# APM9328_CPU.net
KiCad netlist of a schematic drawn in Altium Designer
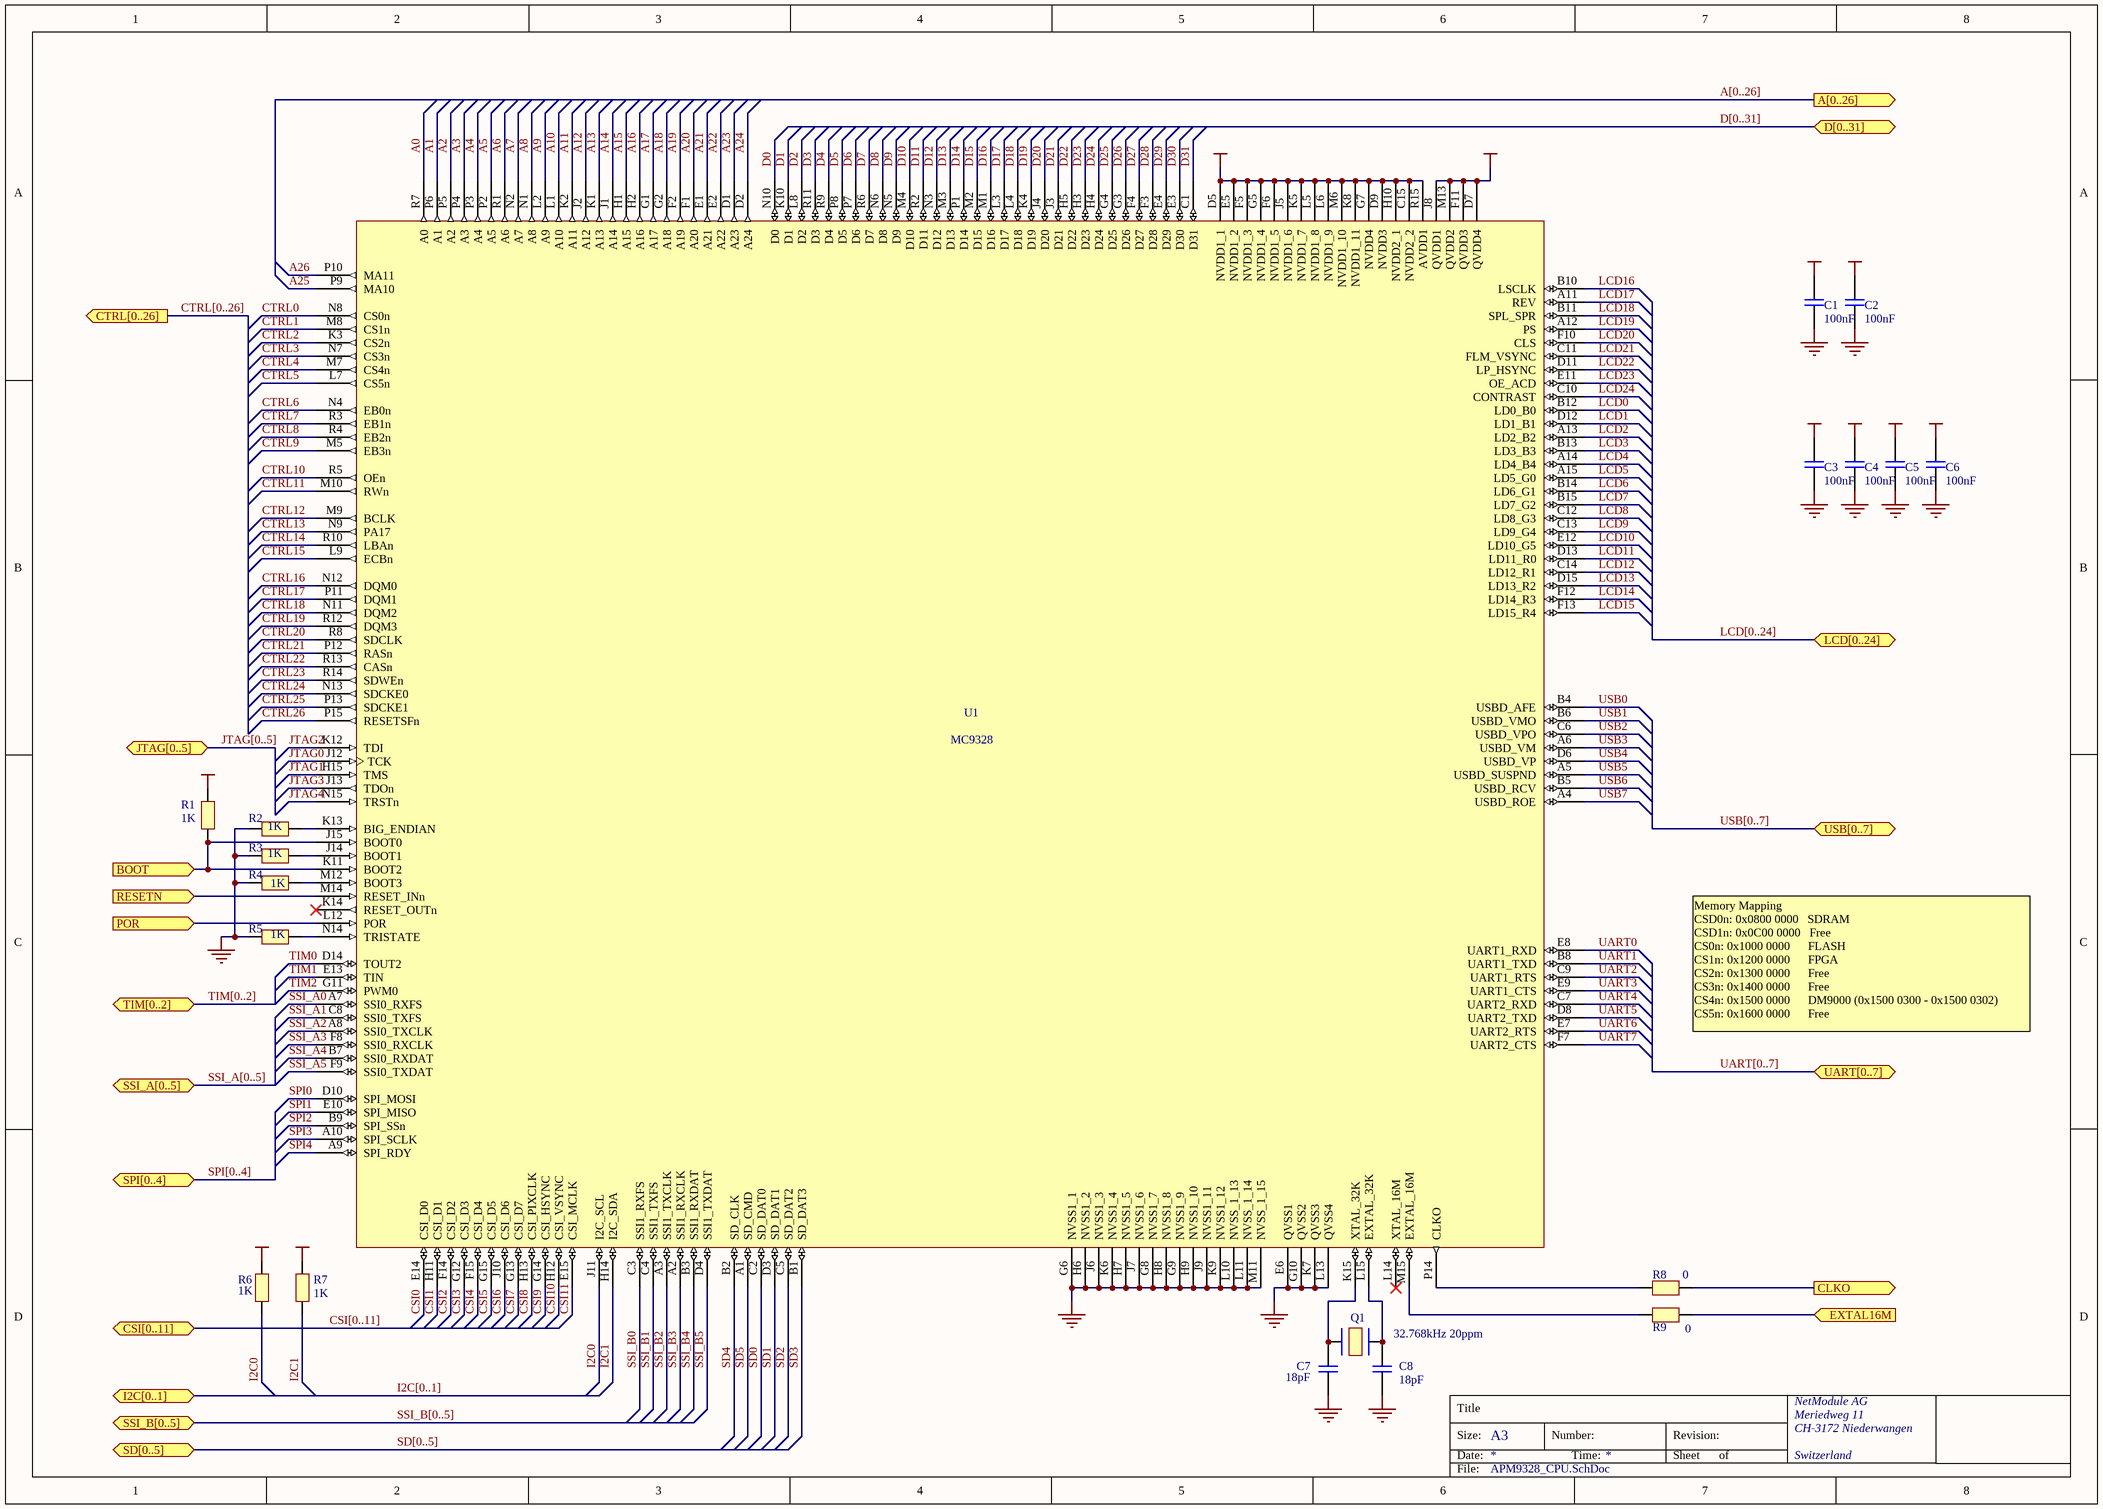
[diagram p0: APM9328_CPU.SchDoc]

(export (version "E")
  (design (tool "Eeschema 10.0.6"))
  (components
    (comp (ref "C1") (value "100nF") (footprint "0402") (libsource (lib "Misc") (part "Cap")))
    (comp (ref "C2") (value "100nF") (footprint "0402") (libsource (lib "Misc") (part "Cap")))
    (comp (ref "C3") (value "100nF") (footprint "0402") (libsource (lib "Misc") (part "Cap")))
    (comp (ref "C4") (value "100nF") (footprint "0402") (libsource (lib "Misc") (part "Cap")))
    (comp (ref "C5") (value "100nF") (footprint "0402") (libsource (lib "Misc") (part "Cap")))
    (comp (ref "C6") (value "100nF") (footprint "0402") (libsource (lib "Misc") (part "Cap")))
    (comp (ref "C7") (value "18pF") (footprint "0402") (libsource (lib "Misc") (part "Cap")))
    (comp (ref "C8") (value "18pF") (footprint "0402") (libsource (lib "Misc") (part "Cap")))
    (comp (ref "Q1")
      (value "32.768kHz 20ppm")
      (footprint "Crystal_SMD_Cyl")
      (description "Quartz")
      (fields (field (name "MANUFACTURER") "Citizen") (field (name "PART NUMBER") "CMR200TB32.768KDZFTR"))
      (libsource (lib "*") (part "QUARTZ"))
    )
    (comp (ref "R1") (value "1K") (footprint "0402") (libsource (lib "") (part "Res_1")))
    (comp (ref "R2") (value "1K") (footprint "0402") (libsource (lib "*") (part "Res")))
    (comp (ref "R3") (value "1K") (footprint "0402") (libsource (lib "*") (part "Res")))
    (comp (ref "R4") (value "1K") (footprint "0402") (libsource (lib "*") (part "Res")))
    (comp (ref "R5") (value "1K") (footprint "0402") (libsource (lib "*") (part "Res")))
    (comp (ref "R6") (value "1K") (footprint "0402") (libsource (lib "") (part "Res_1")))
    (comp (ref "R7") (value "1K") (footprint "0402") (libsource (lib "") (part "Res_1")))
    (comp (ref "R8") (value "0") (footprint "0402") (libsource (lib "*") (part "Res")))
    (comp (ref "R9") (value "0") (footprint "0402") (libsource (lib "*") (part "Res")))
    (comp (ref "U1")
      (value "MC9328")
      (footprint "BGA225x15")
      (fields (field (name "MANUFACTURER") "Freescale"))
      (libsource (lib "Armadeus") (part "MC9328MXL"))
    )
  )
  (nets
    (net (code "2") (name "+1V8") (class "Default")
      (node (ref "C1") (pin "2") (pintype "passive"))
      (node (ref "C2") (pin "2") (pintype "passive"))
      (node (ref "U1") (pin "D7") (pinfunction "QVDD4_D7") (pintype "power_in"))
      (node (ref "U1") (pin "F11") (pinfunction "QVDD3_F11") (pintype "power_in"))
      (node (ref "U1") (pin "J8") (pinfunction "QVDD1_J8") (pintype "power_in"))
      (node (ref "U1") (pin "M13") (pinfunction "QVDD2_M13") (pintype "power_in"))
    )
    (net (code "3") (name "+3V3") (class "Default")
      (node (ref "C3") (pin "2") (pintype "passive"))
      (node (ref "C4") (pin "2") (pintype "passive"))
      (node (ref "C5") (pin "2") (pintype "passive"))
      (node (ref "C6") (pin "2") (pintype "passive"))
      (node (ref "R1") (pin "2") (pintype "passive"))
      (node (ref "R6") (pin "2") (pintype "passive"))
      (node (ref "R7") (pin "2") (pintype "passive"))
      (node (ref "U1") (pin "C15") (pinfunction "NVDD2_2_C15") (pintype "power_in"))
      (node (ref "U1") (pin "D5") (pinfunction "NVDD1_1_D5") (pintype "power_in"))
      (node (ref "U1") (pin "D9") (pinfunction "NVDD3_D9") (pintype "power_in"))
      (node (ref "U1") (pin "E5") (pinfunction "NVDD1_2_E5") (pintype "power_in"))
      (node (ref "U1") (pin "F5") (pinfunction "NVDD1_3_F5") (pintype "power_in"))
      (node (ref "U1") (pin "F6") (pinfunction "NVDD1_5_F6") (pintype "power_in"))
      (node (ref "U1") (pin "G5") (pinfunction "NVDD1_4_G5") (pintype "power_in"))
      (node (ref "U1") (pin "G7") (pinfunction "NVDD4_G7") (pintype "power_in"))
      (node (ref "U1") (pin "H10") (pinfunction "NVDD2_1_H10") (pintype "power_in"))
      (node (ref "U1") (pin "J5") (pinfunction "NVDD1_6_J5") (pintype "power_in"))
      (node (ref "U1") (pin "K5") (pinfunction "NVDD1_7_K5") (pintype "power_in"))
      (node (ref "U1") (pin "K8") (pinfunction "NVDD1_11_K8") (pintype "power_in"))
      (node (ref "U1") (pin "L5") (pinfunction "NVDD1_8_L5") (pintype "power_in"))
      (node (ref "U1") (pin "L6") (pinfunction "NVDD1_9_L6") (pintype "power_in"))
      (node (ref "U1") (pin "M6") (pinfunction "NVDD1_10_M6") (pintype "power_in"))
      (node (ref "U1") (pin "R15") (pinfunction "AVDD1_R15") (pintype "power_in"))
    )
    (net (code "4") (name "/A0") (class "Default")
      (node (ref "U1") (pin "R7") (pinfunction "A0_R7") (pintype "output"))
    )
    (net (code "5") (name "/A1") (class "Default")
      (node (ref "U1") (pin "P6") (pinfunction "A1_P6") (pintype "output"))
    )
    (net (code "6") (name "/A2") (class "Default")
      (node (ref "U1") (pin "P5") (pinfunction "A2_P5") (pintype "output"))
    )
    (net (code "7") (name "/A3") (class "Default")
      (node (ref "U1") (pin "P4") (pinfunction "A3_P4") (pintype "output"))
    )
    (net (code "8") (name "/A4") (class "Default")
      (node (ref "U1") (pin "P3") (pinfunction "A4_P3") (pintype "output"))
    )
    (net (code "9") (name "/A5") (class "Default")
      (node (ref "U1") (pin "P2") (pinfunction "A5_P2") (pintype "output"))
    )
    (net (code "10") (name "/A6") (class "Default")
      (node (ref "U1") (pin "R1") (pinfunction "A6_R1") (pintype "output"))
    )
    (net (code "11") (name "/A7") (class "Default")
      (node (ref "U1") (pin "N2") (pinfunction "A7_N2") (pintype "output"))
    )
    (net (code "12") (name "/A8") (class "Default")
      (node (ref "U1") (pin "N1") (pinfunction "A8_N1") (pintype "output"))
    )
    (net (code "13") (name "/A9") (class "Default")
      (node (ref "U1") (pin "L2") (pinfunction "A9_L2") (pintype "output"))
    )
    (net (code "14") (name "/A10") (class "Default")
      (node (ref "U1") (pin "L1") (pinfunction "A10_L1") (pintype "output"))
    )
    (net (code "15") (name "/A11") (class "Default")
      (node (ref "U1") (pin "K2") (pinfunction "A11_K2") (pintype "output"))
    )
    (net (code "16") (name "/A12") (class "Default")
      (node (ref "U1") (pin "J2") (pinfunction "A12_J2") (pintype "output"))
    )
    (net (code "17") (name "/A13") (class "Default")
      (node (ref "U1") (pin "K1") (pinfunction "A13_K1") (pintype "output"))
    )
    (net (code "18") (name "/A14") (class "Default")
      (node (ref "U1") (pin "J1") (pinfunction "A14_J1") (pintype "output"))
    )
    (net (code "19") (name "/A15") (class "Default")
      (node (ref "U1") (pin "H1") (pinfunction "A15_H1") (pintype "output"))
    )
    (net (code "20") (name "/A16") (class "Default")
      (node (ref "U1") (pin "H2") (pinfunction "A16_H2") (pintype "output"))
    )
    (net (code "21") (name "/A17") (class "Default")
      (node (ref "U1") (pin "G1") (pinfunction "A17_G1") (pintype "output"))
    )
    (net (code "22") (name "/A18") (class "Default")
      (node (ref "U1") (pin "G2") (pinfunction "A18_G2") (pintype "output"))
    )
    (net (code "23") (name "/A19") (class "Default")
      (node (ref "U1") (pin "F2") (pinfunction "A19_F2") (pintype "output"))
    )
    (net (code "24") (name "/A20") (class "Default")
      (node (ref "U1") (pin "F1") (pinfunction "A20_F1") (pintype "output"))
    )
    (net (code "25") (name "/A21") (class "Default")
      (node (ref "U1") (pin "E1") (pinfunction "A21_E1") (pintype "output"))
    )
    (net (code "26") (name "/A22") (class "Default")
      (node (ref "U1") (pin "E2") (pinfunction "A22_E2") (pintype "output"))
    )
    (net (code "27") (name "/A23") (class "Default")
      (node (ref "U1") (pin "D1") (pinfunction "A23_D1") (pintype "output"))
    )
    (net (code "28") (name "/A24") (class "Default")
      (node (ref "U1") (pin "D2") (pinfunction "A24_D2") (pintype "output"))
    )
    (net (code "29") (name "/A25") (class "Default")
      (node (ref "U1") (pin "P9") (pinfunction "MA10_P9") (pintype "output"))
    )
    (net (code "30") (name "/A26") (class "Default")
      (node (ref "U1") (pin "P10") (pinfunction "MA11_P10") (pintype "output"))
    )
    (net (code "32") (name "/BOOT") (class "Default")
      (node (ref "R1") (pin "1") (pintype "passive"))
      (node (ref "U1") (pin "J15") (pinfunction "BOOT0_J15") (pintype "input"))
      (node (ref "U1") (pin "K11") (pinfunction "BOOT2_K11") (pintype "input"))
    )
    (net (code "33") (name "/CLKO") (class "Default") (node (ref "R8") (pin "2") (pintype "passive")))
    (net (code "34") (name "/CSI0") (class "Default")
      (node (ref "U1") (pin "E14") (pinfunction "CSI_D0_E14") (pintype "bidirectional"))
    )
    (net (code "35") (name "/CSI1") (class "Default")
      (node (ref "U1") (pin "H11") (pinfunction "CSI_D1_H11") (pintype "bidirectional"))
    )
    (net (code "36") (name "/CSI2") (class "Default")
      (node (ref "U1") (pin "F14") (pinfunction "CSI_D2_F14") (pintype "bidirectional"))
    )
    (net (code "37") (name "/CSI3") (class "Default")
      (node (ref "U1") (pin "G12") (pinfunction "CSI_D3_G12") (pintype "bidirectional"))
    )
    (net (code "38") (name "/CSI4") (class "Default")
      (node (ref "U1") (pin "F15") (pinfunction "CSI_D4_F15") (pintype "bidirectional"))
    )
    (net (code "39") (name "/CSI5") (class "Default")
      (node (ref "U1") (pin "G15") (pinfunction "CSI_D5_G15") (pintype "bidirectional"))
    )
    (net (code "40") (name "/CSI6") (class "Default")
      (node (ref "U1") (pin "J10") (pinfunction "CSI_D6_J10") (pintype "bidirectional"))
    )
    (net (code "41") (name "/CSI7") (class "Default")
      (node (ref "U1") (pin "G13") (pinfunction "CSI_D7_G13") (pintype "bidirectional"))
    )
    (net (code "42") (name "/CSI8") (class "Default")
      (node (ref "U1") (pin "H13") (pinfunction "CSI_PIXCLK_H13") (pintype "bidirectional"))
    )
    (net (code "43") (name "/CSI9") (class "Default")
      (node (ref "U1") (pin "G14") (pinfunction "CSI_HSYNC_G14") (pintype "bidirectional"))
    )
    (net (code "44") (name "/CSI10") (class "Default")
      (node (ref "U1") (pin "H12") (pinfunction "CSI_VSYNC_H12") (pintype "bidirectional"))
    )
    (net (code "45") (name "/CSI11") (class "Default")
      (node (ref "U1") (pin "E15") (pinfunction "CSI_MCLK_E15") (pintype "bidirectional"))
    )
    (net (code "47") (name "/CTRL0") (class "Default")
      (node (ref "U1") (pin "N8") (pinfunction "CS0n_N8") (pintype "output"))
    )
    (net (code "48") (name "/CTRL1") (class "Default")
      (node (ref "U1") (pin "M8") (pinfunction "CS1n_M8") (pintype "output"))
    )
    (net (code "49") (name "/CTRL2") (class "Default")
      (node (ref "U1") (pin "K3") (pinfunction "CS2n_K3") (pintype "output"))
    )
    (net (code "50") (name "/CTRL3") (class "Default")
      (node (ref "U1") (pin "N7") (pinfunction "CS3n_N7") (pintype "output"))
    )
    (net (code "51") (name "/CTRL4") (class "Default")
      (node (ref "U1") (pin "M7") (pinfunction "CS4n_M7") (pintype "output"))
    )
    (net (code "52") (name "/CTRL5") (class "Default")
      (node (ref "U1") (pin "L7") (pinfunction "CS5n_L7") (pintype "output"))
    )
    (net (code "53") (name "/CTRL6") (class "Default")
      (node (ref "U1") (pin "N4") (pinfunction "EB0n_N4") (pintype "output"))
    )
    (net (code "54") (name "/CTRL7") (class "Default")
      (node (ref "U1") (pin "R3") (pinfunction "EB1n_R3") (pintype "output"))
    )
    (net (code "55") (name "/CTRL8") (class "Default")
      (node (ref "U1") (pin "R4") (pinfunction "EB2n_R4") (pintype "output"))
    )
    (net (code "56") (name "/CTRL9") (class "Default")
      (node (ref "U1") (pin "M5") (pinfunction "EB3n_M5") (pintype "output"))
    )
    (net (code "57") (name "/CTRL10") (class "Default")
      (node (ref "U1") (pin "R5") (pinfunction "OEn_R5") (pintype "output"))
    )
    (net (code "58") (name "/CTRL11") (class "Default")
      (node (ref "U1") (pin "M10") (pinfunction "RWn_M10") (pintype "output"))
    )
    (net (code "59") (name "/CTRL12") (class "Default")
      (node (ref "U1") (pin "M9") (pinfunction "BCLK_M9") (pintype "output"))
    )
    (net (code "60") (name "/CTRL13") (class "Default")
      (node (ref "U1") (pin "N9") (pinfunction "PA17_N9") (pintype "output"))
    )
    (net (code "61") (name "/CTRL14") (class "Default")
      (node (ref "U1") (pin "R10") (pinfunction "LBAn_R10") (pintype "output"))
    )
    (net (code "62") (name "/CTRL15") (class "Default")
      (node (ref "U1") (pin "L9") (pinfunction "ECBn_L9") (pintype "output"))
    )
    (net (code "63") (name "/CTRL16") (class "Default")
      (node (ref "U1") (pin "N12") (pinfunction "DQM0_N12") (pintype "output"))
    )
    (net (code "64") (name "/CTRL17") (class "Default")
      (node (ref "U1") (pin "P11") (pinfunction "DQM1_P11") (pintype "output"))
    )
    (net (code "65") (name "/CTRL18") (class "Default")
      (node (ref "U1") (pin "N11") (pinfunction "DQM2_N11") (pintype "output"))
    )
    (net (code "66") (name "/CTRL19") (class "Default")
      (node (ref "U1") (pin "R12") (pinfunction "DQM3_R12") (pintype "output"))
    )
    (net (code "67") (name "/CTRL20") (class "Default")
      (node (ref "U1") (pin "R8") (pinfunction "SDCLK_R8") (pintype "output"))
    )
    (net (code "68") (name "/CTRL21") (class "Default")
      (node (ref "U1") (pin "P12") (pinfunction "RASn_P12") (pintype "output"))
    )
    (net (code "69") (name "/CTRL22") (class "Default")
      (node (ref "U1") (pin "R13") (pinfunction "CASn_R13") (pintype "output"))
    )
    (net (code "70") (name "/CTRL23") (class "Default")
      (node (ref "U1") (pin "R14") (pinfunction "SDWEn_R14") (pintype "output"))
    )
    (net (code "71") (name "/CTRL24") (class "Default")
      (node (ref "U1") (pin "N13") (pinfunction "SDCKE0_N13") (pintype "output"))
    )
    (net (code "72") (name "/CTRL25") (class "Default")
      (node (ref "U1") (pin "P13") (pinfunction "SDCKE1_P13") (pintype "output"))
    )
    (net (code "73") (name "/CTRL26") (class "Default")
      (node (ref "U1") (pin "P15") (pinfunction "RESETSFn_P15") (pintype "output"))
    )
    (net (code "75") (name "/D0") (class "Default")
      (node (ref "U1") (pin "N10") (pinfunction "D0_N10") (pintype "bidirectional"))
    )
    (net (code "76") (name "/D1") (class "Default")
      (node (ref "U1") (pin "K10") (pinfunction "D1_K10") (pintype "bidirectional"))
    )
    (net (code "77") (name "/D2") (class "Default")
      (node (ref "U1") (pin "L8") (pinfunction "D2_L8") (pintype "bidirectional"))
    )
    (net (code "78") (name "/D3") (class "Default")
      (node (ref "U1") (pin "R11") (pinfunction "D3_R11") (pintype "bidirectional"))
    )
    (net (code "79") (name "/D4") (class "Default")
      (node (ref "U1") (pin "R9") (pinfunction "D4_R9") (pintype "bidirectional"))
    )
    (net (code "80") (name "/D5") (class "Default")
      (node (ref "U1") (pin "P8") (pinfunction "D5_P8") (pintype "bidirectional"))
    )
    (net (code "81") (name "/D6") (class "Default")
      (node (ref "U1") (pin "P7") (pinfunction "D6_P7") (pintype "bidirectional"))
    )
    (net (code "82") (name "/D7") (class "Default")
      (node (ref "U1") (pin "R6") (pinfunction "D7_R6") (pintype "bidirectional"))
    )
    (net (code "83") (name "/D8") (class "Default")
      (node (ref "U1") (pin "N6") (pinfunction "D8_N6") (pintype "bidirectional"))
    )
    (net (code "84") (name "/D9") (class "Default")
      (node (ref "U1") (pin "N5") (pinfunction "D9_N5") (pintype "bidirectional"))
    )
    (net (code "85") (name "/D10") (class "Default")
      (node (ref "U1") (pin "M4") (pinfunction "D10_M4") (pintype "bidirectional"))
    )
    (net (code "86") (name "/D11") (class "Default")
      (node (ref "U1") (pin "R2") (pinfunction "D11_R2") (pintype "bidirectional"))
    )
    (net (code "87") (name "/D12") (class "Default")
      (node (ref "U1") (pin "N3") (pinfunction "D12_N3") (pintype "bidirectional"))
    )
    (net (code "88") (name "/D13") (class "Default")
      (node (ref "U1") (pin "M3") (pinfunction "D13_M3") (pintype "bidirectional"))
    )
    (net (code "89") (name "/D14") (class "Default")
      (node (ref "U1") (pin "P1") (pinfunction "D14_P1") (pintype "bidirectional"))
    )
    (net (code "90") (name "/D15") (class "Default")
      (node (ref "U1") (pin "M2") (pinfunction "D15_M2") (pintype "bidirectional"))
    )
    (net (code "91") (name "/D16") (class "Default")
      (node (ref "U1") (pin "M1") (pinfunction "D16_M1") (pintype "bidirectional"))
    )
    (net (code "92") (name "/D17") (class "Default")
      (node (ref "U1") (pin "L3") (pinfunction "D17_L3") (pintype "bidirectional"))
    )
    (net (code "93") (name "/D18") (class "Default")
      (node (ref "U1") (pin "L4") (pinfunction "D18_L4") (pintype "bidirectional"))
    )
    (net (code "94") (name "/D19") (class "Default")
      (node (ref "U1") (pin "K4") (pinfunction "D19_K4") (pintype "bidirectional"))
    )
    (net (code "95") (name "/D20") (class "Default")
      (node (ref "U1") (pin "J4") (pinfunction "D20_J4") (pintype "bidirectional"))
    )
    (net (code "96") (name "/D21") (class "Default")
      (node (ref "U1") (pin "J3") (pinfunction "D21_J3") (pintype "bidirectional"))
    )
    (net (code "97") (name "/D22") (class "Default")
      (node (ref "U1") (pin "H5") (pinfunction "D22_H5") (pintype "bidirectional"))
    )
    (net (code "98") (name "/D23") (class "Default")
      (node (ref "U1") (pin "H3") (pinfunction "D23_H3") (pintype "bidirectional"))
    )
    (net (code "99") (name "/D24") (class "Default")
      (node (ref "U1") (pin "H4") (pinfunction "D24_H4") (pintype "bidirectional"))
    )
    (net (code "100") (name "/D25") (class "Default")
      (node (ref "U1") (pin "G4") (pinfunction "D25_G4") (pintype "bidirectional"))
    )
    (net (code "101") (name "/D26") (class "Default")
      (node (ref "U1") (pin "G3") (pinfunction "D26_G3") (pintype "bidirectional"))
    )
    (net (code "102") (name "/D27") (class "Default")
      (node (ref "U1") (pin "F4") (pinfunction "D27_F4") (pintype "bidirectional"))
    )
    (net (code "103") (name "/D28") (class "Default")
      (node (ref "U1") (pin "F3") (pinfunction "D28_F3") (pintype "bidirectional"))
    )
    (net (code "104") (name "/D29") (class "Default")
      (node (ref "U1") (pin "E4") (pinfunction "D29_E4") (pintype "bidirectional"))
    )
    (net (code "105") (name "/D30") (class "Default")
      (node (ref "U1") (pin "E3") (pinfunction "D30_E3") (pintype "bidirectional"))
    )
    (net (code "106") (name "/D31") (class "Default")
      (node (ref "U1") (pin "C1") (pinfunction "D31_C1") (pintype "bidirectional"))
    )
    (net (code "108") (name "/EXTAL16M") (class "Default") (node (ref "R9") (pin "2") (pintype "passive")))
    (net (code "109") (name "/I2C0") (class "Default")
      (node (ref "R6") (pin "1") (pintype "passive"))
      (node (ref "U1") (pin "J11") (pinfunction "I2C_SCL_J11") (pintype "bidirectional"))
    )
    (net (code "110") (name "/I2C1") (class "Default")
      (node (ref "R7") (pin "1") (pintype "passive"))
      (node (ref "U1") (pin "H14") (pinfunction "I2C_SDA_H14") (pintype "bidirectional"))
    )
    (net (code "112") (name "/JTAG0") (class "Default")
      (node (ref "U1") (pin "J12") (pinfunction "TCK_J12") (pintype "input"))
    )
    (net (code "113") (name "/JTAG1") (class "Default")
      (node (ref "U1") (pin "H15") (pinfunction "TMS_H15") (pintype "input"))
    )
    (net (code "114") (name "/JTAG2") (class "Default")
      (node (ref "U1") (pin "K12") (pinfunction "TDI_K12") (pintype "input"))
    )
    (net (code "115") (name "/JTAG3") (class "Default")
      (node (ref "U1") (pin "J13") (pinfunction "TDOn_J13") (pintype "output"))
    )
    (net (code "116") (name "/JTAG4") (class "Default")
      (node (ref "U1") (pin "N15") (pinfunction "TRSTn_N15") (pintype "input"))
    )
    (net (code "118") (name "/LCD0") (class "Default")
      (node (ref "U1") (pin "B12") (pinfunction "LD0_B0_B12") (pintype "bidirectional"))
    )
    (net (code "119") (name "/LCD1") (class "Default")
      (node (ref "U1") (pin "D12") (pinfunction "LD1_B1_D12") (pintype "bidirectional"))
    )
    (net (code "120") (name "/LCD2") (class "Default")
      (node (ref "U1") (pin "A13") (pinfunction "LD2_B2_A13") (pintype "bidirectional"))
    )
    (net (code "121") (name "/LCD3") (class "Default")
      (node (ref "U1") (pin "B13") (pinfunction "LD3_B3_B13") (pintype "bidirectional"))
    )
    (net (code "122") (name "/LCD4") (class "Default")
      (node (ref "U1") (pin "A14") (pinfunction "LD4_B4_A14") (pintype "bidirectional"))
    )
    (net (code "123") (name "/LCD5") (class "Default")
      (node (ref "U1") (pin "A15") (pinfunction "LD5_G0_A15") (pintype "bidirectional"))
    )
    (net (code "124") (name "/LCD6") (class "Default")
      (node (ref "U1") (pin "B14") (pinfunction "LD6_G1_B14") (pintype "bidirectional"))
    )
    (net (code "125") (name "/LCD7") (class "Default")
      (node (ref "U1") (pin "B15") (pinfunction "LD7_G2_B15") (pintype "bidirectional"))
    )
    (net (code "126") (name "/LCD8") (class "Default")
      (node (ref "U1") (pin "C12") (pinfunction "LD8_G3_C12") (pintype "bidirectional"))
    )
    (net (code "127") (name "/LCD9") (class "Default")
      (node (ref "U1") (pin "C13") (pinfunction "LD9_G4_C13") (pintype "bidirectional"))
    )
    (net (code "128") (name "/LCD10") (class "Default")
      (node (ref "U1") (pin "E12") (pinfunction "LD10_G5_E12") (pintype "bidirectional"))
    )
    (net (code "129") (name "/LCD11") (class "Default")
      (node (ref "U1") (pin "D13") (pinfunction "LD11_R0_D13") (pintype "bidirectional"))
    )
    (net (code "130") (name "/LCD12") (class "Default")
      (node (ref "U1") (pin "C14") (pinfunction "LD12_R1_C14") (pintype "bidirectional"))
    )
    (net (code "131") (name "/LCD13") (class "Default")
      (node (ref "U1") (pin "D15") (pinfunction "LD13_R2_D15") (pintype "bidirectional"))
    )
    (net (code "132") (name "/LCD14") (class "Default")
      (node (ref "U1") (pin "F12") (pinfunction "LD14_R3_F12") (pintype "bidirectional"))
    )
    (net (code "133") (name "/LCD15") (class "Default")
      (node (ref "U1") (pin "F13") (pinfunction "LD15_R4_F13") (pintype "bidirectional"))
    )
    (net (code "134") (name "/LCD16") (class "Default")
      (node (ref "U1") (pin "B10") (pinfunction "LSCLK_B10") (pintype "bidirectional"))
    )
    (net (code "135") (name "/LCD17") (class "Default")
      (node (ref "U1") (pin "A11") (pinfunction "REV_A11") (pintype "bidirectional"))
    )
    (net (code "136") (name "/LCD18") (class "Default")
      (node (ref "U1") (pin "B11") (pinfunction "SPL_SPR_B11") (pintype "bidirectional"))
    )
    (net (code "137") (name "/LCD19") (class "Default")
      (node (ref "U1") (pin "A12") (pinfunction "PS_A12") (pintype "bidirectional"))
    )
    (net (code "138") (name "/LCD20") (class "Default")
      (node (ref "U1") (pin "F10") (pinfunction "CLS_F10") (pintype "bidirectional"))
    )
    (net (code "139") (name "/LCD21") (class "Default")
      (node (ref "U1") (pin "C11") (pinfunction "FLM_VSYNC_C11") (pintype "bidirectional"))
    )
    (net (code "140") (name "/LCD22") (class "Default")
      (node (ref "U1") (pin "D11") (pinfunction "LP_HSYNC_D11") (pintype "bidirectional"))
    )
    (net (code "141") (name "/LCD23") (class "Default")
      (node (ref "U1") (pin "E11") (pinfunction "OE_ACD_E11") (pintype "bidirectional"))
    )
    (net (code "142") (name "/LCD24") (class "Default")
      (node (ref "U1") (pin "C10") (pinfunction "CONTRAST_C10") (pintype "bidirectional"))
    )
    (net (code "144") (name "/POR") (class "Default")
      (node (ref "U1") (pin "L12") (pinfunction "POR_L12") (pintype "input"))
    )
    (net (code "145") (name "/RESETN") (class "Default")
      (node (ref "U1") (pin "M14") (pinfunction "RESET_INn_M14") (pintype "input"))
    )
    (net (code "146") (name "/SD0") (class "Default")
      (node (ref "U1") (pin "C2") (pinfunction "SD_DAT0_C2") (pintype "bidirectional"))
    )
    (net (code "147") (name "/SD1") (class "Default")
      (node (ref "U1") (pin "D3") (pinfunction "SD_DAT1_D3") (pintype "bidirectional"))
    )
    (net (code "148") (name "/SD2") (class "Default")
      (node (ref "U1") (pin "C5") (pinfunction "SD_DAT2_C5") (pintype "bidirectional"))
    )
    (net (code "149") (name "/SD3") (class "Default")
      (node (ref "U1") (pin "B1") (pinfunction "SD_DAT3_B1") (pintype "bidirectional"))
    )
    (net (code "150") (name "/SD4") (class "Default")
      (node (ref "U1") (pin "B2") (pinfunction "SD_CLK_B2") (pintype "bidirectional"))
    )
    (net (code "151") (name "/SD5") (class "Default")
      (node (ref "U1") (pin "A1") (pinfunction "SD_CMD_A1") (pintype "bidirectional"))
    )
    (net (code "153") (name "/SPI0") (class "Default")
      (node (ref "U1") (pin "D10") (pinfunction "SPI_MOSI_D10") (pintype "bidirectional"))
    )
    (net (code "154") (name "/SPI1") (class "Default")
      (node (ref "U1") (pin "E10") (pinfunction "SPI_MISO_E10") (pintype "bidirectional"))
    )
    (net (code "155") (name "/SPI2") (class "Default")
      (node (ref "U1") (pin "B9") (pinfunction "SPI_SSn_B9") (pintype "bidirectional"))
    )
    (net (code "156") (name "/SPI3") (class "Default")
      (node (ref "U1") (pin "A10") (pinfunction "SPI_SCLK_A10") (pintype "bidirectional"))
    )
    (net (code "157") (name "/SPI4") (class "Default")
      (node (ref "U1") (pin "A9") (pinfunction "SPI_RDY_A9") (pintype "bidirectional"))
    )
    (net (code "159") (name "/SSI_A0") (class "Default")
      (node (ref "U1") (pin "A7") (pinfunction "SSI0_RXFS_A7") (pintype "bidirectional"))
    )
    (net (code "160") (name "/SSI_A1") (class "Default")
      (node (ref "U1") (pin "C8") (pinfunction "SSI0_TXFS_C8") (pintype "bidirectional"))
    )
    (net (code "161") (name "/SSI_A2") (class "Default")
      (node (ref "U1") (pin "A8") (pinfunction "SSI0_TXCLK_A8") (pintype "bidirectional"))
    )
    (net (code "162") (name "/SSI_A3") (class "Default")
      (node (ref "U1") (pin "F8") (pinfunction "SSI0_RXCLK_F8") (pintype "bidirectional"))
    )
    (net (code "163") (name "/SSI_A4") (class "Default")
      (node (ref "U1") (pin "B7") (pinfunction "SSI0_RXDAT_B7") (pintype "bidirectional"))
    )
    (net (code "164") (name "/SSI_A5") (class "Default")
      (node (ref "U1") (pin "F9") (pinfunction "SSI0_TXDAT_F9") (pintype "bidirectional"))
    )
    (net (code "166") (name "/SSI_B0") (class "Default")
      (node (ref "U1") (pin "C3") (pinfunction "SSI1_RXFS_C3") (pintype "bidirectional"))
    )
    (net (code "167") (name "/SSI_B1") (class "Default")
      (node (ref "U1") (pin "C4") (pinfunction "SSI1_TXFS_C4") (pintype "bidirectional"))
    )
    (net (code "168") (name "/SSI_B2") (class "Default")
      (node (ref "U1") (pin "A3") (pinfunction "SSI1_TXCLK_A3") (pintype "bidirectional"))
    )
    (net (code "169") (name "/SSI_B3") (class "Default")
      (node (ref "U1") (pin "A2") (pinfunction "SSI1_RXCLK_A2") (pintype "bidirectional"))
    )
    (net (code "170") (name "/SSI_B4") (class "Default")
      (node (ref "U1") (pin "B3") (pinfunction "SSI1_RXDAT_B3") (pintype "bidirectional"))
    )
    (net (code "171") (name "/SSI_B5") (class "Default")
      (node (ref "U1") (pin "D4") (pinfunction "SSI1_TXDAT_D4") (pintype "bidirectional"))
    )
    (net (code "173") (name "/TIM0") (class "Default")
      (node (ref "U1") (pin "D14") (pinfunction "TOUT2_D14") (pintype "bidirectional"))
    )
    (net (code "174") (name "/TIM1") (class "Default")
      (node (ref "U1") (pin "E13") (pinfunction "TIN_E13") (pintype "bidirectional"))
    )
    (net (code "175") (name "/TIM2") (class "Default")
      (node (ref "U1") (pin "G11") (pinfunction "PWM0_G11") (pintype "bidirectional"))
    )
    (net (code "177") (name "/UART0") (class "Default")
      (node (ref "U1") (pin "E8") (pinfunction "UART1_RXD_E8") (pintype "bidirectional"))
    )
    (net (code "178") (name "/UART1") (class "Default")
      (node (ref "U1") (pin "B8") (pinfunction "UART1_TXD_B8") (pintype "bidirectional"))
    )
    (net (code "179") (name "/UART2") (class "Default")
      (node (ref "U1") (pin "C9") (pinfunction "UART1_RTS_C9") (pintype "bidirectional"))
    )
    (net (code "180") (name "/UART3") (class "Default")
      (node (ref "U1") (pin "E9") (pinfunction "UART1_CTS_E9") (pintype "bidirectional"))
    )
    (net (code "181") (name "/UART4") (class "Default")
      (node (ref "U1") (pin "C7") (pinfunction "UART2_RXD_C7") (pintype "bidirectional"))
    )
    (net (code "182") (name "/UART5") (class "Default")
      (node (ref "U1") (pin "D8") (pinfunction "UART2_TXD_D8") (pintype "bidirectional"))
    )
    (net (code "183") (name "/UART6") (class "Default")
      (node (ref "U1") (pin "E7") (pinfunction "UART2_RTS_E7") (pintype "bidirectional"))
    )
    (net (code "184") (name "/UART7") (class "Default")
      (node (ref "U1") (pin "F7") (pinfunction "UART2_CTS_F7") (pintype "bidirectional"))
    )
    (net (code "186") (name "/USB0") (class "Default")
      (node (ref "U1") (pin "B4") (pinfunction "USBD_AFE_B4") (pintype "bidirectional"))
    )
    (net (code "187") (name "/USB1") (class "Default")
      (node (ref "U1") (pin "B6") (pinfunction "USBD_VMO_B6") (pintype "bidirectional"))
    )
    (net (code "188") (name "/USB2") (class "Default")
      (node (ref "U1") (pin "C6") (pinfunction "USBD_VPO_C6") (pintype "bidirectional"))
    )
    (net (code "189") (name "/USB3") (class "Default")
      (node (ref "U1") (pin "A6") (pinfunction "USBD_VM_A6") (pintype "bidirectional"))
    )
    (net (code "190") (name "/USB4") (class "Default")
      (node (ref "U1") (pin "D6") (pinfunction "USBD_VP_D6") (pintype "bidirectional"))
    )
    (net (code "191") (name "/USB5") (class "Default")
      (node (ref "U1") (pin "A5") (pinfunction "USBD_SUSPND_A5") (pintype "bidirectional"))
    )
    (net (code "192") (name "/USB6") (class "Default")
      (node (ref "U1") (pin "B5") (pinfunction "USBD_RCV_B5") (pintype "bidirectional"))
    )
    (net (code "193") (name "/USB7") (class "Default")
      (node (ref "U1") (pin "A4") (pinfunction "USBD_ROE_A4") (pintype "bidirectional"))
    )
    (net (code "195") (name "GND") (class "Default")
      (node (ref "C1") (pin "1") (pintype "passive"))
      (node (ref "C2") (pin "1") (pintype "passive"))
      (node (ref "C3") (pin "1") (pintype "passive"))
      (node (ref "C4") (pin "1") (pintype "passive"))
      (node (ref "C5") (pin "1") (pintype "passive"))
      (node (ref "C6") (pin "1") (pintype "passive"))
      (node (ref "C7") (pin "1") (pintype "passive"))
      (node (ref "C8") (pin "1") (pintype "passive"))
      (node (ref "R2") (pin "1") (pintype "passive"))
      (node (ref "R3") (pin "1") (pintype "passive"))
      (node (ref "R4") (pin "1") (pintype "passive"))
      (node (ref "R5") (pin "1") (pintype "passive"))
      (node (ref "U1") (pin "E6") (pinfunction "QVSS1_E6") (pintype "power_in"))
      (node (ref "U1") (pin "G10") (pinfunction "QVSS2_G10") (pintype "power_in"))
      (node (ref "U1") (pin "G6") (pinfunction "NVSS1_1_G6") (pintype "power_in"))
      (node (ref "U1") (pin "G8") (pinfunction "NVSS1_7_G8") (pintype "power_in"))
      (node (ref "U1") (pin "G9") (pinfunction "NVSS1_9_G9") (pintype "power_in"))
      (node (ref "U1") (pin "H6") (pinfunction "NVSS1_2_H6") (pintype "power_in"))
      (node (ref "U1") (pin "H7") (pinfunction "NVSS1_5_H7") (pintype "power_in"))
      (node (ref "U1") (pin "H8") (pinfunction "NVSS1_8_H8") (pintype "power_in"))
      (node (ref "U1") (pin "H9") (pinfunction "NVSS1_10_H9") (pintype "power_in"))
      (node (ref "U1") (pin "J6") (pinfunction "NVSS1_3_J6") (pintype "power_in"))
      (node (ref "U1") (pin "J7") (pinfunction "NVSS1_6_J7") (pintype "power_in"))
      (node (ref "U1") (pin "J9") (pinfunction "NVSS1_11_J9") (pintype "power_in"))
      (node (ref "U1") (pin "K6") (pinfunction "NVSS1_4_K6") (pintype "power_in"))
      (node (ref "U1") (pin "K7") (pinfunction "QVSS3_K7") (pintype "power_in"))
      (node (ref "U1") (pin "K9") (pinfunction "NVSS1_12_K9") (pintype "power_in"))
      (node (ref "U1") (pin "L10") (pinfunction "NVSS_1_13_L10") (pintype "power_in"))
      (node (ref "U1") (pin "L11") (pinfunction "NVSS_1_14_L11") (pintype "power_in"))
      (node (ref "U1") (pin "L13") (pinfunction "QVSS4_L13") (pintype "power_in"))
      (node (ref "U1") (pin "M11") (pinfunction "NVSS_1_15_M11") (pintype "power_in"))
    )
    (net (code "196") (name "Net-(U1-BIG_ENDIAN)") (class "Default")
      (node (ref "R2") (pin "2") (pintype "passive"))
      (node (ref "U1") (pin "K13") (pinfunction "BIG_ENDIAN_K13") (pintype "input"))
    )
    (net (code "197") (name "Net-(U1-BOOT1)") (class "Default")
      (node (ref "R3") (pin "2") (pintype "passive"))
      (node (ref "U1") (pin "J14") (pinfunction "BOOT1_J14") (pintype "input"))
    )
    (net (code "198") (name "Net-(U1-BOOT3)") (class "Default")
      (node (ref "R4") (pin "2") (pintype "passive"))
      (node (ref "U1") (pin "M12") (pinfunction "BOOT3_M12") (pintype "input"))
    )
    (net (code "199") (name "Net-(U1-CLKO)") (class "Default")
      (node (ref "R8") (pin "1") (pintype "passive"))
      (node (ref "U1") (pin "P14") (pinfunction "CLKO_P14") (pintype "output"))
    )
    (net (code "200") (name "Net-(U1-EXTAL_16M)") (class "Default")
      (node (ref "R9") (pin "1") (pintype "passive"))
      (node (ref "U1") (pin "M15") (pinfunction "EXTAL_16M_M15") (pintype "bidirectional"))
    )
    (net (code "201") (name "Net-(U1-EXTAL_32K)") (class "Default")
      (node (ref "C8") (pin "2") (pintype "passive"))
      (node (ref "Q1") (pin "2") (pintype "passive"))
      (node (ref "U1") (pin "L15") (pinfunction "EXTAL_32K_L15") (pintype "bidirectional"))
    )
    (net (code "202") (name "Net-(U1-TRISTATE)") (class "Default")
      (node (ref "R5") (pin "2") (pintype "passive"))
      (node (ref "U1") (pin "N14") (pinfunction "TRISTATE_N14") (pintype "input"))
    )
    (net (code "203") (name "Net-(U1-XTAL_32K)") (class "Default")
      (node (ref "C7") (pin "2") (pintype "passive"))
      (node (ref "Q1") (pin "1") (pintype "passive"))
      (node (ref "U1") (pin "K15") (pinfunction "XTAL_32K_K15") (pintype "bidirectional"))
    )
    (net (code "204") (name "unconnected-(U1-RESET_OUTn-PadK14)") (class "Default")
      (node (ref "U1") (pin "K14") (pinfunction "RESET_OUTn_K14") (pintype "output+no_connect"))
    )
    (net (code "205") (name "unconnected-(U1-XTAL_16M-PadL14)") (class "Default")
      (node (ref "U1") (pin "L14") (pinfunction "XTAL_16M_L14") (pintype "bidirectional+no_connect"))
    )
  )
)
